# prototype1-with-charging-circut.net
KiCad netlist of a schematic drawn in EAGLE
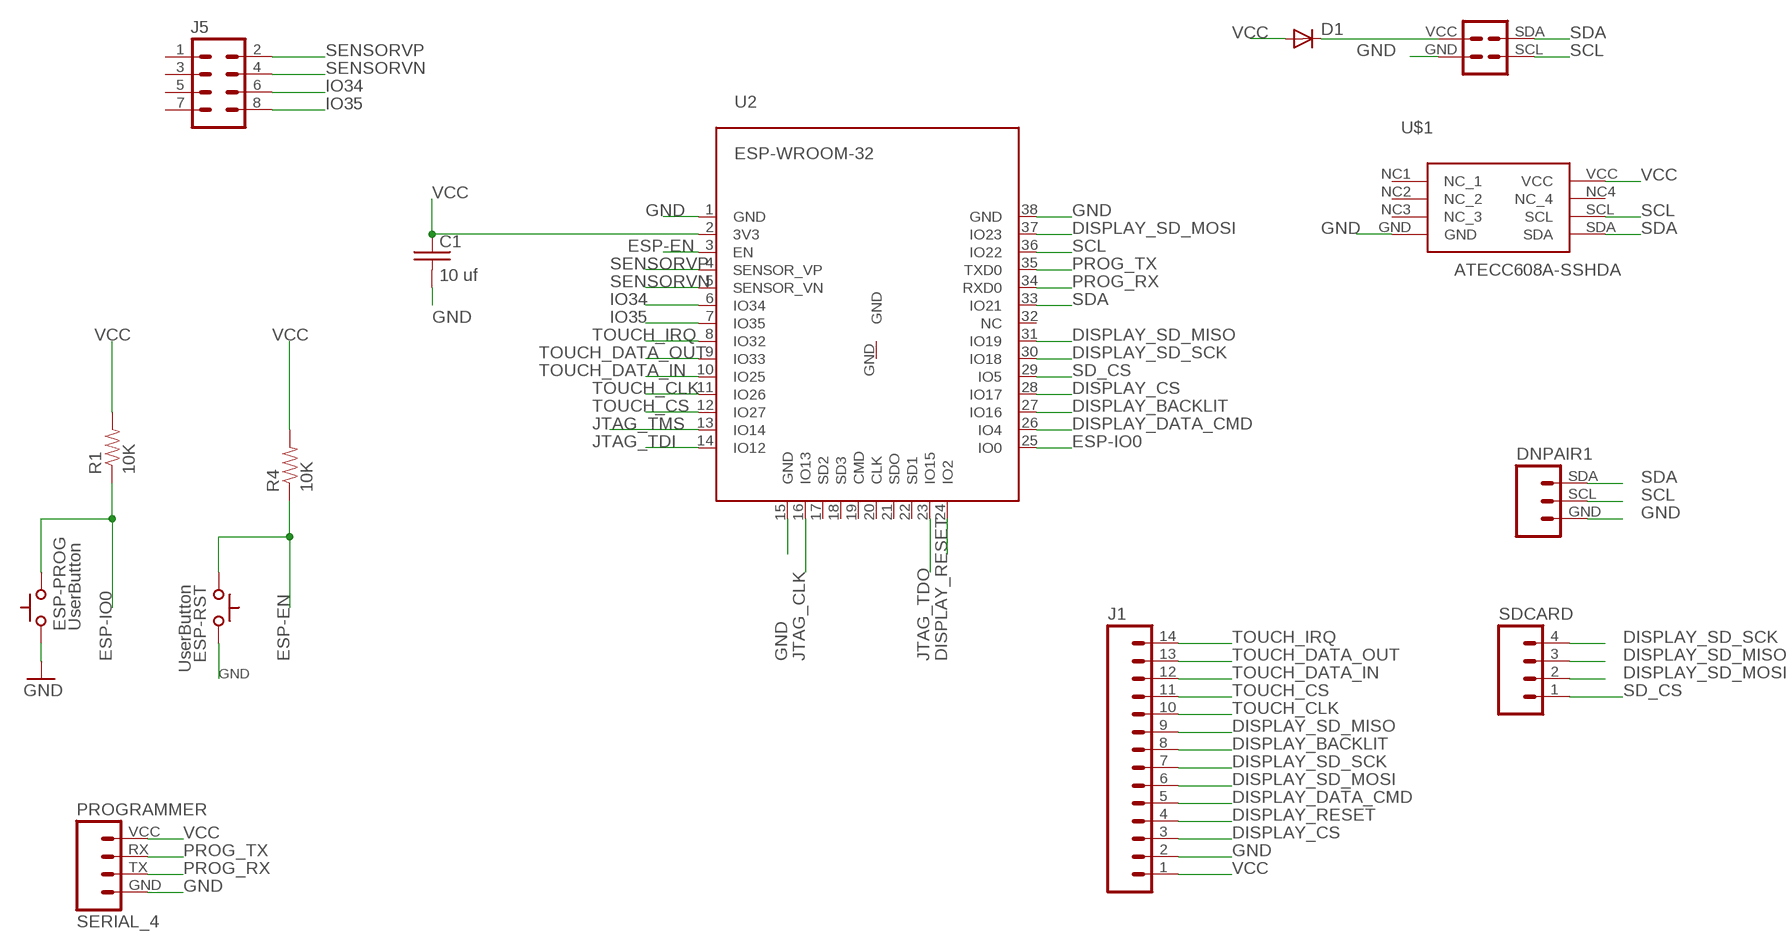
[diagram p0: schematic, sheet 1]
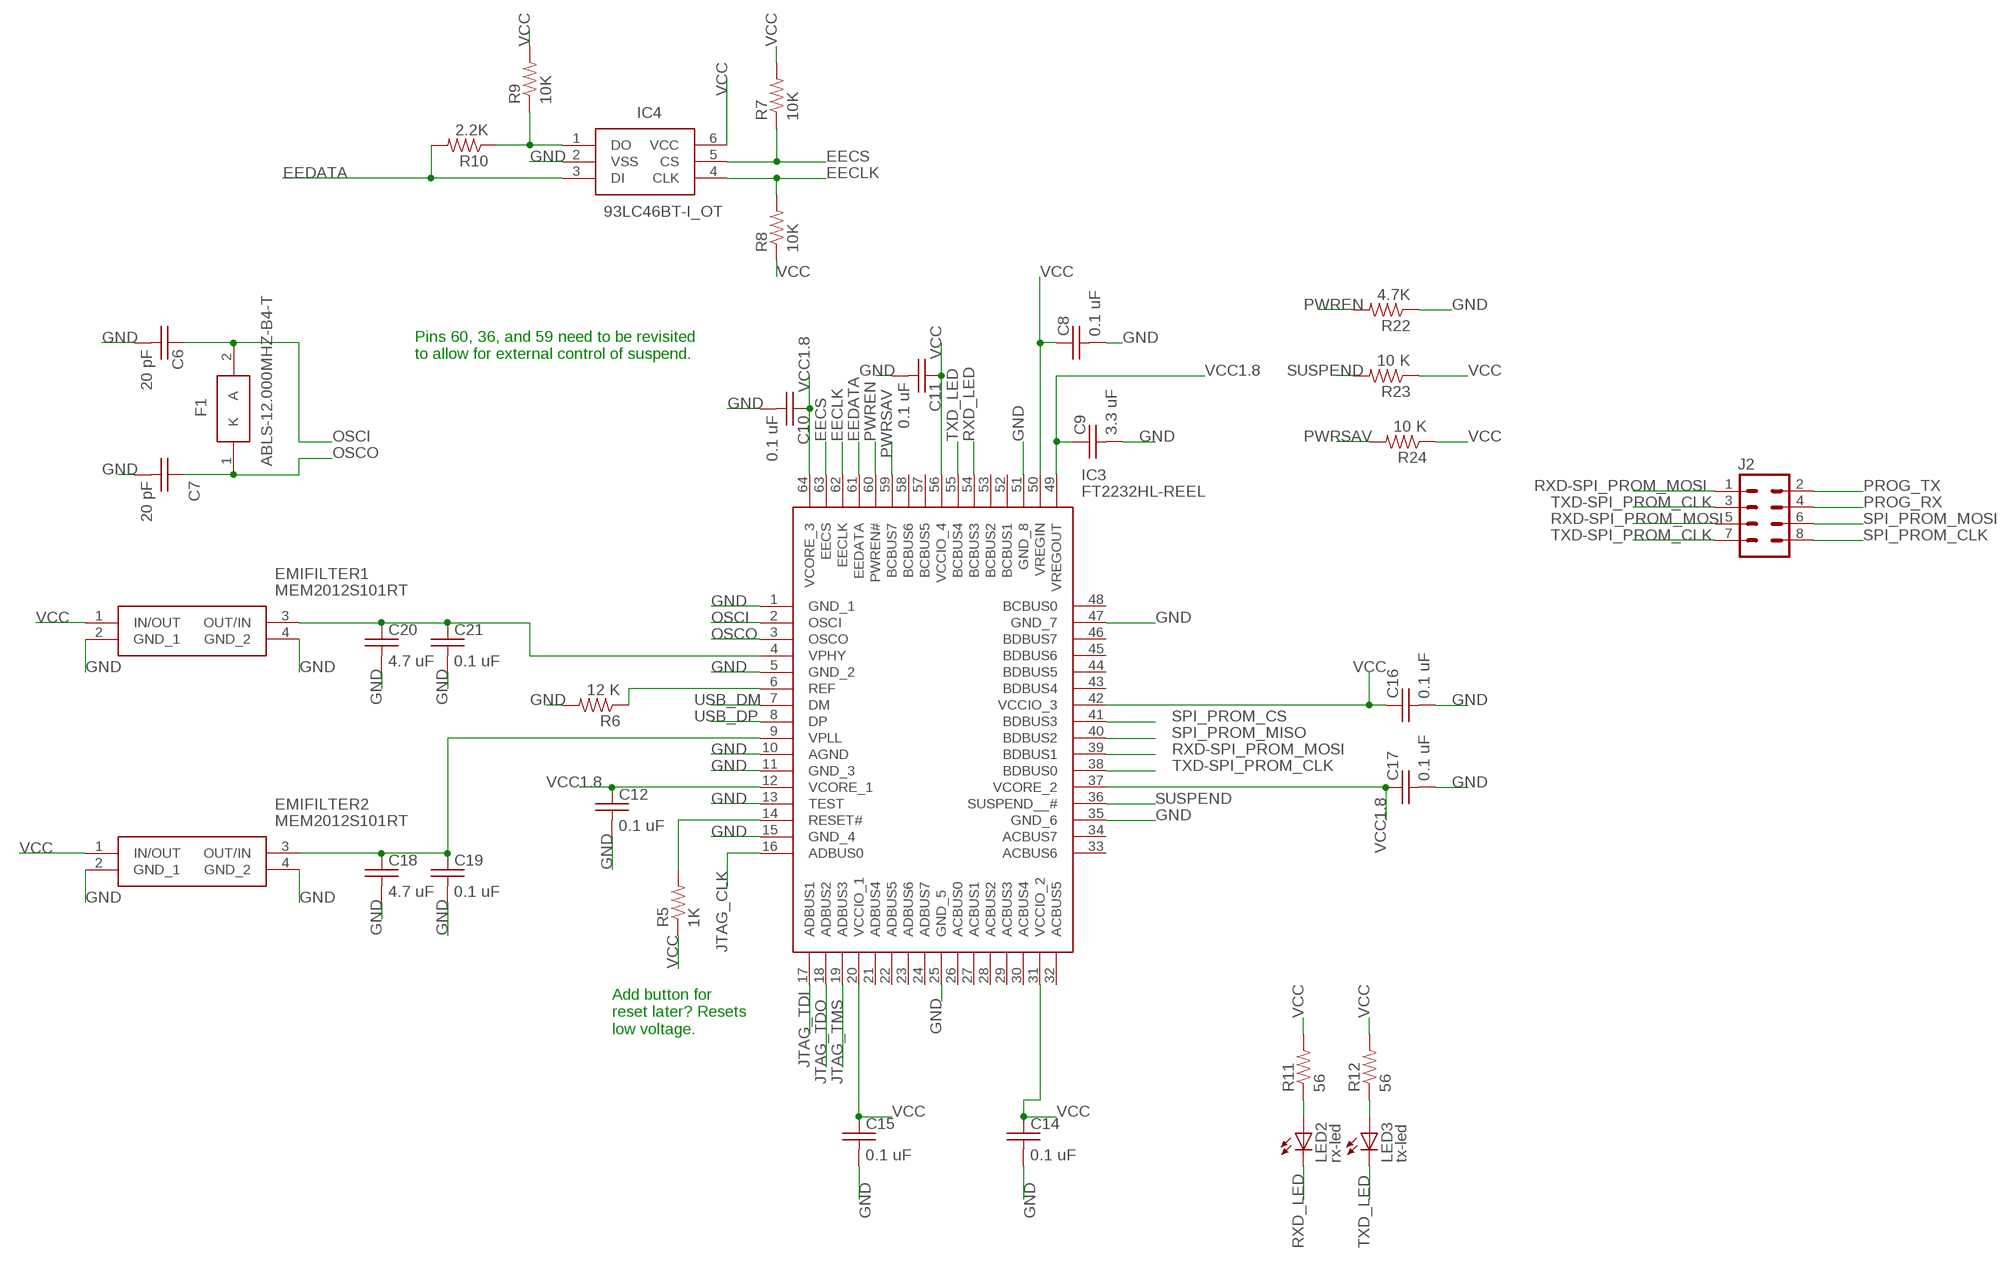
[diagram p1: schematic, sheet 2]
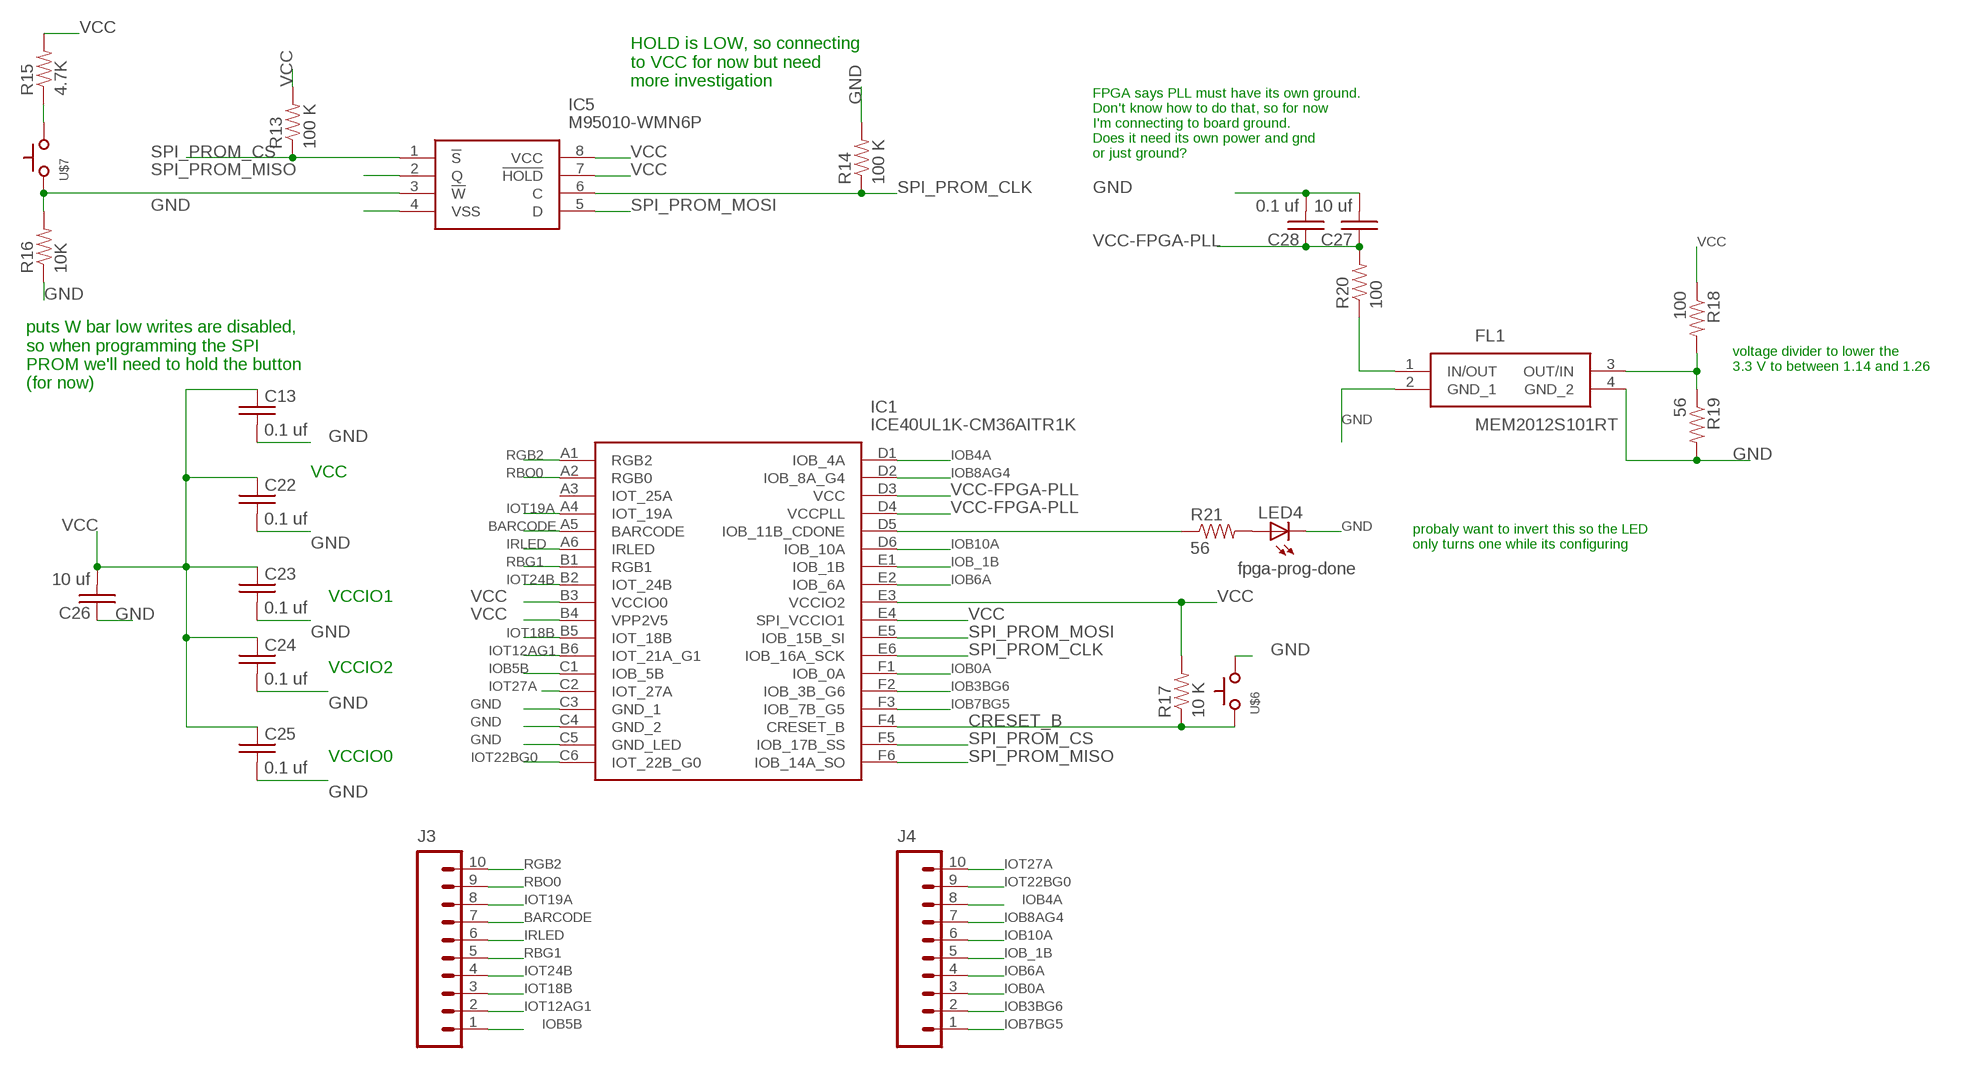
[diagram p2: schematic, sheet 3]
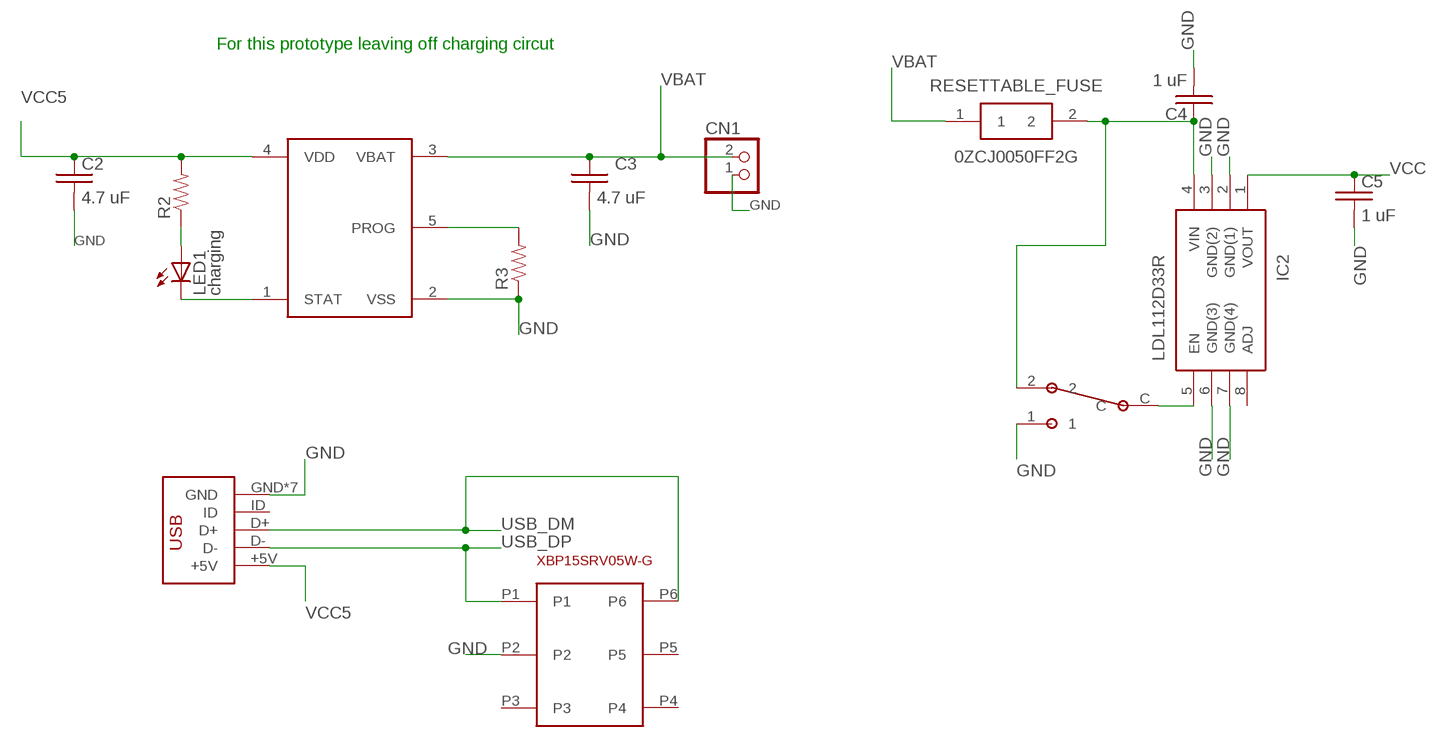
[diagram p3: schematic, sheet 4]

(export (version "E")
  (design (tool "Eeschema 10.0.6"))
  (components
    (comp (ref "C6")
      (value "20 pF")
      (footprint "eagle-import:C0805")
      (libsource (lib "eagle-import") (part "C-USC0805"))
    )
    (comp (ref "C7")
      (value "20 pF")
      (footprint "eagle-import:C0805")
      (libsource (lib "eagle-import") (part "C-USC0805"))
    )
    (comp (ref "C8")
      (value "0.1 uF")
      (footprint "eagle-import:C0805")
      (libsource (lib "eagle-import") (part "C-USC0805"))
    )
    (comp (ref "C9")
      (value "3.3 uF")
      (footprint "eagle-import:C0805")
      (libsource (lib "eagle-import") (part "C-USC0805"))
    )
    (comp (ref "C10")
      (value "0.1 uF")
      (footprint "eagle-import:C0805")
      (libsource (lib "eagle-import") (part "C-USC0805"))
    )
    (comp (ref "C11")
      (value "0.1 uF")
      (footprint "eagle-import:C0805")
      (libsource (lib "eagle-import") (part "C-USC0805"))
    )
    (comp (ref "C12")
      (value "0.1 uF")
      (footprint "eagle-import:C0805")
      (libsource (lib "eagle-import") (part "C-USC0805"))
    )
    (comp (ref "C14")
      (value "0.1 uF")
      (footprint "eagle-import:C0805")
      (libsource (lib "eagle-import") (part "C-USC0805"))
    )
    (comp (ref "C15")
      (value "0.1 uF")
      (footprint "eagle-import:C0805")
      (libsource (lib "eagle-import") (part "C-USC0805"))
    )
    (comp (ref "C16")
      (value "0.1 uF")
      (footprint "eagle-import:C0805")
      (libsource (lib "eagle-import") (part "C-USC0805"))
    )
    (comp (ref "C17")
      (value "0.1 uF")
      (footprint "eagle-import:C0805")
      (libsource (lib "eagle-import") (part "C-USC0805"))
    )
    (comp (ref "C18")
      (value "4.7 uF")
      (footprint "eagle-import:C0805")
      (libsource (lib "eagle-import") (part "C-USC0805"))
    )
    (comp (ref "C19")
      (value "0.1 uF")
      (footprint "eagle-import:C0805")
      (libsource (lib "eagle-import") (part "C-USC0805"))
    )
    (comp (ref "C20")
      (value "4.7 uF")
      (footprint "eagle-import:C0805")
      (libsource (lib "eagle-import") (part "C-USC0805"))
    )
    (comp (ref "C21")
      (value "0.1 uF")
      (footprint "eagle-import:C0805")
      (libsource (lib "eagle-import") (part "C-USC0805"))
    )
    (comp (ref "EMIFILTER1")
      (value "MEM2012S101RT")
      (footprint "eagle-import:MEM2012S101RT")
      (libsource (lib "eagle-import") (part "MEM2012S101RT"))
    )
    (comp (ref "EMIFILTER2")
      (value "MEM2012S101RT")
      (footprint "eagle-import:MEM2012S101RT")
      (libsource (lib "eagle-import") (part "MEM2012S101RT"))
    )
    (comp (ref "F1")
      (value "ABLS-12.000MHZ-B4-T")
      (footprint "eagle-import:HC_49US-(AT49)_1")
      (fields
        (field (name "MOUSER_PART_NUMBER") "815-ABLS-12.0M-T")
        (field (name "RS_PART_NUMBER") "1710207")
      )
      (libsource (lib "eagle-import") (part "ABLS-12.000MHZ-B4-T"))
    )
    (comp (ref "IC3")
      (value "FT2232HL-REEL")
      (footprint "eagle-import:QFP50P1200X1200X160-64N")
      (fields (field (name "MOUSER_PART_NUMBER") "895-FT2232HL"))
      (libsource (lib "eagle-import") (part "FT2232HL-REEL"))
    )
    (comp (ref "IC4")
      (value "93LC46BT-I_OT")
      (footprint "eagle-import:SOT95P270X145-6N")
      (fields
        (field (name "MANUFACTURER_PART_NUMBER") "93LC46BT-I/OT")
        (field (name "MOUSER_PART_NUMBER") "579-93LC46BT-I/OT")
      )
      (libsource (lib "eagle-import") (part "93LC46BT-I_OT"))
    )
    (comp (ref "J2")
      (value "M04X2")
      (footprint "eagle-import:2X4")
      (libsource (lib "eagle-import") (part "M04X2"))
    )
    (comp (ref "LED2")
      (value "rx-led")
      (footprint "eagle-import:LED3MM")
      (libsource (lib "eagle-import") (part "LED3MM"))
    )
    (comp (ref "LED3")
      (value "tx-led")
      (footprint "eagle-import:LED3MM")
      (libsource (lib "eagle-import") (part "LED3MM"))
    )
    (comp (ref "R5")
      (value "1K")
      (footprint "eagle-import:0805")
      (libsource (lib "eagle-import") (part "passives_RESISTOR0805-RES"))
    )
    (comp (ref "R6")
      (value "12 K")
      (footprint "eagle-import:0805")
      (libsource (lib "eagle-import") (part "passives_RESISTOR0805-RES"))
    )
    (comp (ref "R7")
      (value "10K")
      (footprint "eagle-import:0805")
      (libsource (lib "eagle-import") (part "passives_RESISTOR0805-RES"))
    )
    (comp (ref "R8")
      (value "10K")
      (footprint "eagle-import:0805")
      (libsource (lib "eagle-import") (part "passives_RESISTOR0805-RES"))
    )
    (comp (ref "R9")
      (value "10K")
      (footprint "eagle-import:0805")
      (libsource (lib "eagle-import") (part "passives_RESISTOR0805-RES"))
    )
    (comp (ref "R10")
      (value "2.2K")
      (footprint "eagle-import:0805")
      (libsource (lib "eagle-import") (part "passives_RESISTOR0805-RES"))
    )
    (comp (ref "R11")
      (value "56")
      (footprint "eagle-import:0805")
      (libsource (lib "eagle-import") (part "passives_RESISTOR0805-RES"))
    )
    (comp (ref "R12")
      (value "56")
      (footprint "eagle-import:0805")
      (libsource (lib "eagle-import") (part "passives_RESISTOR0805-RES"))
    )
    (comp (ref "R22")
      (value "4.7K")
      (footprint "eagle-import:0805")
      (libsource (lib "eagle-import") (part "passives_RESISTOR0805-RES"))
    )
    (comp (ref "R23")
      (value "10 K")
      (footprint "eagle-import:0805")
      (libsource (lib "eagle-import") (part "passives_RESISTOR0805-RES"))
    )
    (comp (ref "R24")
      (value "10 K")
      (footprint "eagle-import:0805")
      (libsource (lib "eagle-import") (part "passives_RESISTOR0805-RES"))
    )
    (comp (ref "C13")
      (value "0.1 uf")
      (footprint "eagle-import:C0805")
      (libsource (lib "eagle-import") (part "C-USC0805"))
    )
    (comp (ref "C22")
      (value "0.1 uf")
      (footprint "eagle-import:C0805")
      (libsource (lib "eagle-import") (part "C-USC0805"))
    )
    (comp (ref "C23")
      (value "0.1 uf")
      (footprint "eagle-import:C0805")
      (libsource (lib "eagle-import") (part "C-USC0805"))
    )
    (comp (ref "C24")
      (value "0.1 uf")
      (footprint "eagle-import:C0805")
      (libsource (lib "eagle-import") (part "C-USC0805"))
    )
    (comp (ref "C25")
      (value "0.1 uf")
      (footprint "eagle-import:C0805")
      (libsource (lib "eagle-import") (part "C-USC0805"))
    )
    (comp (ref "C26")
      (value "10 uf")
      (footprint "eagle-import:C0805")
      (libsource (lib "eagle-import") (part "C-USC0805"))
    )
    (comp (ref "C27")
      (value "10 uf")
      (footprint "eagle-import:C0805")
      (libsource (lib "eagle-import") (part "C-USC0805"))
    )
    (comp (ref "C28")
      (value "0.1 uf")
      (footprint "eagle-import:C0805")
      (libsource (lib "eagle-import") (part "C-USC0805"))
    )
    (comp (ref "FL1")
      (value "MEM2012S101RT")
      (footprint "eagle-import:MEM2012S101RT")
      (libsource (lib "eagle-import") (part "MEM2012S101RT"))
    )
    (comp (ref "IC1")
      (value "ICE40UL1K-CM36AITR1K")
      (footprint "eagle-import:BGA36C40P6X6_250X250X91")
      (fields (field (name "MOUSER_PART_NUMBER") "842-40UL1KCM36AITR1K"))
      (libsource (lib "eagle-import") (part "ICE40UL1K-CM36AITR1K"))
    )
    (comp (ref "IC5")
      (value "M95010-WMN6P")
      (footprint "eagle-import:SOIC127P600X175-8N")
      (fields
        (field (name "MOUSER_PART_NUMBER") "511-M95010-WMN6P")
        (field (name "RS_PART_NUMBER") "7147617")
      )
      (libsource (lib "eagle-import") (part "M95010-WMN6P"))
    )
    (comp (ref "J3")
      (value "M10SILK_FEMALE_PTH")
      (footprint "eagle-import:1X10")
      (libsource (lib "eagle-import") (part "M10SILK_FEMALE_PTH"))
    )
    (comp (ref "J4")
      (value "M10SILK_FEMALE_PTH")
      (footprint "eagle-import:1X10")
      (libsource (lib "eagle-import") (part "M10SILK_FEMALE_PTH"))
    )
    (comp (ref "LED4")
      (value "fpga-prog-done")
      (footprint "eagle-import:LED3MM")
      (libsource (lib "eagle-import") (part "LED3MM"))
    )
    (comp (ref "R13")
      (value "100 K")
      (footprint "eagle-import:0805")
      (libsource (lib "eagle-import") (part "passives_RESISTOR0805-RES"))
    )
    (comp (ref "R14")
      (value "100 K")
      (footprint "eagle-import:0805")
      (libsource (lib "eagle-import") (part "passives_RESISTOR0805-RES"))
    )
    (comp (ref "R15")
      (value "4.7K")
      (footprint "eagle-import:0805")
      (libsource (lib "eagle-import") (part "passives_RESISTOR0805-RES"))
    )
    (comp (ref "R16")
      (value "10K")
      (footprint "eagle-import:0805")
      (libsource (lib "eagle-import") (part "passives_RESISTOR0805-RES"))
    )
    (comp (ref "R17")
      (value "10 K")
      (footprint "eagle-import:0805")
      (libsource (lib "eagle-import") (part "passives_RESISTOR0805-RES"))
    )
    (comp (ref "R18")
      (value "100")
      (footprint "eagle-import:0805")
      (libsource (lib "eagle-import") (part "passives_RESISTOR0805-RES"))
    )
    (comp (ref "R19")
      (value "56")
      (footprint "eagle-import:0805")
      (libsource (lib "eagle-import") (part "passives_RESISTOR0805-RES"))
    )
    (comp (ref "R20")
      (value "100")
      (footprint "eagle-import:0805")
      (libsource (lib "eagle-import") (part "passives_RESISTOR0805-RES"))
    )
    (comp (ref "R21")
      (value "56")
      (footprint "eagle-import:0805")
      (libsource (lib "eagle-import") (part "passives_RESISTOR0805-RES"))
    )
    (comp (ref "U$6")
      (value "SWITCH_TACTILETACTILE-2PIN")
      (footprint "eagle-import:TACTILE-2PIN")
      (libsource (lib "eagle-import") (part "switches_SWITCH_TACTILETACTILE-2PIN"))
    )
    (comp (ref "U$7")
      (value "SWITCH_TACTILETACTILE-2PIN")
      (footprint "eagle-import:TACTILE-2PIN")
      (libsource (lib "eagle-import") (part "switches_SWITCH_TACTILETACTILE-2PIN"))
    )
    (comp (ref "C1")
      (value "10 uf")
      (footprint "eagle-import:C0805")
      (libsource (lib "eagle-import") (part "C-USC0805"))
    )
    (comp (ref "D1")
      (value "DIODESMA")
      (footprint "eagle-import:SMA-DIODE")
      (libsource (lib "eagle-import") (part "DIODESMA"))
    )
    (comp (ref "DNPAIR1")
      (value "DARKNET_8_PAIR_CONNECTORPTH")
      (footprint "eagle-import:1X03")
      (libsource (lib "eagle-import") (part "DARKNET_8_PAIR_CONNECTORPTH"))
    )
    (comp (ref "ESP-PROG")
      (value "UserButton")
      (footprint "eagle-import:TACTILE-2PIN-NARROW")
      (libsource (lib "eagle-import") (part "SWITCH_TACTILETACTILE-2PIN-NARROW"))
    )
    (comp (ref "ESP-RST")
      (value "UserButton")
      (footprint "eagle-import:TACTILE-2PIN-NARROW")
      (libsource (lib "eagle-import") (part "SWITCH_TACTILETACTILE-2PIN-NARROW"))
    )
    (comp (ref "J1")
      (value "M14")
      (footprint "eagle-import:1X14")
      (libsource (lib "eagle-import") (part "M14"))
    )
    (comp (ref "J5")
      (value "M04X2")
      (footprint "eagle-import:2X4")
      (libsource (lib "eagle-import") (part "M04X2"))
    )
    (comp (ref "PROGRAMMER")
      (value "SERIAL_4")
      (footprint "eagle-import:SERIAL_HEADER_4")
      (libsource (lib "eagle-import") (part "SERIAL_4"))
    )
    (comp (ref "R1")
      (value "10K")
      (footprint "eagle-import:0805")
      (libsource (lib "eagle-import") (part "RESISTOR0805-RES"))
    )
    (comp (ref "R4")
      (value "10K")
      (footprint "eagle-import:0805")
      (libsource (lib "eagle-import") (part "RESISTOR0805-RES"))
    )
    (comp (ref "SDCARD")
      (value "M04PTH")
      (footprint "eagle-import:1X04")
      (libsource (lib "eagle-import") (part "M04PTH"))
    )
    (comp (ref "SHITTY_ADDON")
      (value "SAO1")
      (footprint "eagle-import:DC26SHITTY_ADDON_CONNECTOR")
      (libsource (lib "eagle-import") (part "DC26_SHITTY_ADDON_CONNECTORPTH"))
    )
    (comp (ref "U$1")
      (value "ATECC608A-SSHDA")
      (footprint "eagle-import:8-SOIC")
      (libsource (lib "eagle-import") (part "ATECC608A-SSHDA"))
    )
    (comp (ref "U2")
      (value "ESP-WROOM-32")
      (footprint "eagle-import:ESP-WROOM-32")
      (libsource (lib "eagle-import") (part "ESP-WROOM-32"))
    )
    (comp (ref "C2")
      (value "4.7 uF")
      (footprint "eagle-import:C0805")
      (libsource (lib "eagle-import") (part "C-USC0805"))
    )
    (comp (ref "C3")
      (value "4.7 uF")
      (footprint "eagle-import:C0805")
      (libsource (lib "eagle-import") (part "C-USC0805"))
    )
    (comp (ref "C4")
      (value "1 uF")
      (footprint "eagle-import:C0805")
      (libsource (lib "eagle-import") (part "C-USC0805"))
    )
    (comp (ref "C5")
      (value "1 uF")
      (footprint "eagle-import:C0805")
      (libsource (lib "eagle-import") (part "C-USC0805"))
    )
    (comp (ref "CN1")
      (value "JST_2PIN-THM-RA")
      (footprint "eagle-import:JST-PH-2-THM-RA")
      (libsource (lib "eagle-import") (part "JST_2PIN-THM-RA"))
    )
    (comp (ref "IC2")
      (value "LDL112D33R")
      (footprint "eagle-import:SOIC127P600X175-8N")
      (libsource (lib "eagle-import") (part "LDL112D33R"))
    )
    (comp (ref "LED1")
      (value "charging")
      (footprint "eagle-import:LED-0603")
      (libsource (lib "eagle-import") (part "LED0603"))
    )
    (comp (ref "R2")
      (value "RESISTOR0805-RES")
      (footprint "eagle-import:0805")
      (libsource (lib "eagle-import") (part "passives_RESISTOR0805-RES"))
    )
    (comp (ref "R3")
      (value "RESISTOR0805-RES")
      (footprint "eagle-import:0805")
      (libsource (lib "eagle-import") (part "passives_RESISTOR0805-RES"))
    )
    (comp (ref "RESETTABLE_FUSE")
      (value "0ZCJ0050FF2G")
      (footprint "eagle-import:FUSC3216X55N")
      (libsource (lib "eagle-import") (part "0ZCJ0050FF2G"))
    )
    (comp (ref "U$2")
      (value "DX4R005JJ2DX4R005JJ2")
      (footprint "eagle-import:DX4R005JJ2")
      (libsource (lib "eagle-import") (part "DX4R005JJ2DX4R005JJ2"))
    )
    (comp (ref "U$3")
      (value "XBP15SRV05W-G")
      (footprint "eagle-import:SOT-26P-XBP15SRV05W-G")
      (fields (field (name "DIGI_KEY_PART_NUMBER") "893-1422-1-ND"))
      (libsource (lib "eagle-import") (part "XBP15SRV05W-G"))
    )
    (comp (ref "U$4")
      (value "DS21984E")
      (footprint "eagle-import:SOT23-5")
      (libsource (lib "eagle-import") (part "DS21984E"))
    )
    (comp (ref "U$5")
      (value "SWITCH_SPDT")
      (footprint "eagle-import:SPDT_SSAJ120100")
      (libsource (lib "eagle-import") (part "SWITCH_SPDT"))
    )
  )
  (nets
    (net (code "1") (name "BARCODE") (class "Default")
      (node (ref "IC1") (pin "A5") (pinfunction "BARCODE_A5") (pintype "bidirectional"))
      (node (ref "J3") (pin "7") (pinfunction "7_7") (pintype "passive"))
    )
    (net (code "2") (name "CRESET_B") (class "Default")
      (node (ref "IC1") (pin "F4") (pinfunction "CRESET_B_F4") (pintype "bidirectional"))
      (node (ref "R17") (pin "1") (pinfunction "1_1") (pintype "passive"))
      (node (ref "U$6") (pin "P$2") (pinfunction "C_P$2") (pintype "passive"))
    )
    (net (code "3") (name "DISPLAY_BACKLIT") (class "Default")
      (node (ref "J1") (pin "8") (pinfunction "8_8") (pintype "passive"))
      (node (ref "U2") (pin "27") (pinfunction "IO16_27") (pintype "bidirectional"))
    )
    (net (code "4") (name "DISPLAY_CS") (class "Default")
      (node (ref "J1") (pin "3") (pinfunction "3_3") (pintype "passive"))
      (node (ref "U2") (pin "28") (pinfunction "IO17_28") (pintype "bidirectional"))
    )
    (net (code "5") (name "DISPLAY_DATA_CMD") (class "Default")
      (node (ref "J1") (pin "5") (pinfunction "5_5") (pintype "passive"))
      (node (ref "U2") (pin "26") (pinfunction "IO4_26") (pintype "bidirectional"))
    )
    (net (code "6") (name "DISPLAY_RESET") (class "Default")
      (node (ref "J1") (pin "4") (pinfunction "4_4") (pintype "passive"))
      (node (ref "U2") (pin "24") (pinfunction "IO2_24") (pintype "bidirectional"))
    )
    (net (code "7") (name "DISPLAY_SD_MISO") (class "Default")
      (node (ref "J1") (pin "9") (pinfunction "9_9") (pintype "passive"))
      (node (ref "SDCARD") (pin "3") (pinfunction "3_3") (pintype "passive"))
      (node (ref "U2") (pin "31") (pinfunction "IO19_31") (pintype "bidirectional"))
    )
    (net (code "8") (name "DISPLAY_SD_MOSI") (class "Default")
      (node (ref "J1") (pin "6") (pinfunction "6_6") (pintype "passive"))
      (node (ref "SDCARD") (pin "2") (pinfunction "2_2") (pintype "passive"))
      (node (ref "U2") (pin "37") (pinfunction "IO23_37") (pintype "bidirectional"))
    )
    (net (code "9") (name "DISPLAY_SD_SCK") (class "Default")
      (node (ref "J1") (pin "7") (pinfunction "7_7") (pintype "passive"))
      (node (ref "SDCARD") (pin "4") (pinfunction "4_4") (pintype "passive"))
      (node (ref "U2") (pin "30") (pinfunction "IO18_30") (pintype "bidirectional"))
    )
    (net (code "10") (name "EECLK") (class "Default")
      (node (ref "IC3") (pin "62") (pinfunction "EECLK_62") (pintype "bidirectional"))
      (node (ref "IC4") (pin "4") (pinfunction "CLK_4") (pintype "input"))
      (node (ref "R8") (pin "2") (pinfunction "2_2") (pintype "passive"))
    )
    (net (code "11") (name "EECS") (class "Default")
      (node (ref "IC3") (pin "63") (pinfunction "EECS_63") (pintype "bidirectional"))
      (node (ref "IC4") (pin "5") (pinfunction "CS_5") (pintype "input"))
      (node (ref "R7") (pin "1") (pinfunction "1_1") (pintype "passive"))
    )
    (net (code "12") (name "EEDATA") (class "Default")
      (node (ref "IC3") (pin "61") (pinfunction "EEDATA_61") (pintype "bidirectional"))
      (node (ref "IC4") (pin "3") (pinfunction "DI_3") (pintype "bidirectional"))
      (node (ref "R10") (pin "2") (pinfunction "2_2") (pintype "passive"))
    )
    (net (code "13") (name "ESP-EN") (class "Default")
      (node (ref "ESP-RST") (pin "P$2") (pinfunction "C_P$2") (pintype "passive"))
      (node (ref "R4") (pin "1") (pinfunction "1_1") (pintype "passive"))
      (node (ref "U2") (pin "3") (pinfunction "EN_3") (pintype "bidirectional"))
    )
    (net (code "14") (name "ESP-IO0") (class "Default")
      (node (ref "ESP-PROG") (pin "P$1") (pinfunction "A_P$1") (pintype "passive"))
      (node (ref "R1") (pin "1") (pinfunction "1_1") (pintype "passive"))
      (node (ref "U2") (pin "25") (pinfunction "IO0_25") (pintype "bidirectional"))
    )
    (net (code "15") (name "GND") (class "Default")
      (node (ref "C1") (pin "2") (pinfunction "2_2") (pintype "passive"))
      (node (ref "C10") (pin "2") (pinfunction "2_2") (pintype "passive"))
      (node (ref "C11") (pin "2") (pinfunction "2_2") (pintype "passive"))
      (node (ref "C12") (pin "2") (pinfunction "2_2") (pintype "passive"))
      (node (ref "C13") (pin "2") (pinfunction "2_2") (pintype "passive"))
      (node (ref "C14") (pin "2") (pinfunction "2_2") (pintype "passive"))
      (node (ref "C15") (pin "2") (pinfunction "2_2") (pintype "passive"))
      (node (ref "C16") (pin "2") (pinfunction "2_2") (pintype "passive"))
      (node (ref "C17") (pin "2") (pinfunction "2_2") (pintype "passive"))
      (node (ref "C18") (pin "2") (pinfunction "2_2") (pintype "passive"))
      (node (ref "C19") (pin "2") (pinfunction "2_2") (pintype "passive"))
      (node (ref "C2") (pin "2") (pinfunction "2_2") (pintype "passive"))
      (node (ref "C20") (pin "2") (pinfunction "2_2") (pintype "passive"))
      (node (ref "C21") (pin "2") (pinfunction "2_2") (pintype "passive"))
      (node (ref "C22") (pin "2") (pinfunction "2_2") (pintype "passive"))
      (node (ref "C23") (pin "2") (pinfunction "2_2") (pintype "passive"))
      (node (ref "C24") (pin "2") (pinfunction "2_2") (pintype "passive"))
      (node (ref "C25") (pin "2") (pinfunction "2_2") (pintype "passive"))
      (node (ref "C26") (pin "1") (pinfunction "1_1") (pintype "passive"))
      (node (ref "C27") (pin "2") (pinfunction "2_2") (pintype "passive"))
      (node (ref "C28") (pin "2") (pinfunction "2_2") (pintype "passive"))
      (node (ref "C3") (pin "2") (pinfunction "2_2") (pintype "passive"))
      (node (ref "C4") (pin "2") (pinfunction "2_2") (pintype "passive"))
      (node (ref "C5") (pin "2") (pinfunction "2_2") (pintype "passive"))
      (node (ref "C6") (pin "2") (pinfunction "2_2") (pintype "passive"))
      (node (ref "C7") (pin "2") (pinfunction "2_2") (pintype "passive"))
      (node (ref "C8") (pin "2") (pinfunction "2_2") (pintype "passive"))
      (node (ref "C9") (pin "2") (pinfunction "2_2") (pintype "passive"))
      (node (ref "CN1") (pin "1") (pinfunction "2_1") (pintype "passive"))
      (node (ref "DNPAIR1") (pin "GND") (pinfunction "GND_GND") (pintype "power_in"))
      (node (ref "EMIFILTER1") (pin "2") (pinfunction "GND_1_2") (pintype "bidirectional"))
      (node (ref "EMIFILTER1") (pin "4") (pinfunction "GND_2_4") (pintype "bidirectional"))
      (node (ref "EMIFILTER2") (pin "2") (pinfunction "GND_1_2") (pintype "bidirectional"))
      (node (ref "EMIFILTER2") (pin "4") (pinfunction "GND_2_4") (pintype "bidirectional"))
      (node (ref "ESP-PROG") (pin "P$2") (pinfunction "C_P$2") (pintype "passive"))
      (node (ref "ESP-RST") (pin "P$1") (pinfunction "A_P$1") (pintype "passive"))
      (node (ref "FL1") (pin "2") (pinfunction "GND_1_2") (pintype "bidirectional"))
      (node (ref "FL1") (pin "4") (pinfunction "GND_2_4") (pintype "bidirectional"))
      (node (ref "IC1") (pin "C3") (pinfunction "GND_1_C3") (pintype "bidirectional"))
      (node (ref "IC1") (pin "C4") (pinfunction "GND_2_C4") (pintype "bidirectional"))
      (node (ref "IC1") (pin "C5") (pinfunction "GND_LED_C5") (pintype "bidirectional"))
      (node (ref "IC2") (pin "2") (pinfunction "GND(1)_2") (pintype "bidirectional"))
      (node (ref "IC2") (pin "3") (pinfunction "GND(2)_3") (pintype "bidirectional"))
      (node (ref "IC2") (pin "6") (pinfunction "GND(3)_6") (pintype "bidirectional"))
      (node (ref "IC2") (pin "7") (pinfunction "GND(4)_7") (pintype "bidirectional"))
      (node (ref "IC3") (pin "1") (pinfunction "GND_1_1") (pintype "bidirectional"))
      (node (ref "IC3") (pin "10") (pinfunction "AGND_10") (pintype "bidirectional"))
      (node (ref "IC3") (pin "11") (pinfunction "GND_3_11") (pintype "bidirectional"))
      (node (ref "IC3") (pin "13") (pinfunction "TEST_13") (pintype "bidirectional"))
      (node (ref "IC3") (pin "15") (pinfunction "GND_4_15") (pintype "bidirectional"))
      (node (ref "IC3") (pin "25") (pinfunction "GND_5_25") (pintype "bidirectional"))
      (node (ref "IC3") (pin "35") (pinfunction "GND_6_35") (pintype "bidirectional"))
      (node (ref "IC3") (pin "47") (pinfunction "GND_7_47") (pintype "bidirectional"))
      (node (ref "IC3") (pin "5") (pinfunction "GND_2_5") (pintype "bidirectional"))
      (node (ref "IC3") (pin "51") (pinfunction "GND_8_51") (pintype "bidirectional"))
      (node (ref "IC4") (pin "2") (pinfunction "VSS_2") (pintype "power_in"))
      (node (ref "IC5") (pin "4") (pinfunction "VSS_4") (pintype "power_in"))
      (node (ref "J1") (pin "2") (pinfunction "2_2") (pintype "passive"))
      (node (ref "LED4") (pin "K") (pinfunction "C_K") (pintype "output"))
      (node (ref "PROGRAMMER") (pin "GND") (pinfunction "GND_GND") (pintype "power_in"))
      (node (ref "R14") (pin "2") (pinfunction "2_2") (pintype "passive"))
      (node (ref "R16") (pin "1") (pinfunction "1_1") (pintype "passive"))
      (node (ref "R19") (pin "2") (pinfunction "2_2") (pintype "passive"))
      (node (ref "R22") (pin "1") (pinfunction "1_1") (pintype "passive"))
      (node (ref "R3") (pin "1") (pinfunction "1_1") (pintype "passive"))
      (node (ref "R6") (pin "2") (pinfunction "2_2") (pintype "passive"))
      (node (ref "SHITTY_ADDON") (pin "GND") (pinfunction "GND_GND") (pintype "power_in"))
      (node (ref "U$1") (pin "GND") (pinfunction "GND_GND") (pintype "power_in"))
      (node (ref "U$2") (pin "GND") (pinfunction "GND_GND") (pintype "bidirectional"))
      (node (ref "U$2") (pin "P$10") (pinfunction "GND_P$10") (pintype "bidirectional"))
      (node (ref "U$2") (pin "P$11") (pinfunction "GND_P$11") (pintype "bidirectional"))
      (node (ref "U$2") (pin "P$6") (pinfunction "GND_P$6") (pintype "bidirectional"))
      (node (ref "U$2") (pin "P$7") (pinfunction "GND_P$7") (pintype "bidirectional"))
      (node (ref "U$2") (pin "P$8") (pinfunction "GND_P$8") (pintype "bidirectional"))
      (node (ref "U$2") (pin "P$9") (pinfunction "GND_P$9") (pintype "bidirectional"))
      (node (ref "U$3") (pin "P2") (pinfunction "P2_P2") (pintype "bidirectional"))
      (node (ref "U$4") (pin "2") (pinfunction "VSS_2") (pintype "bidirectional"))
      (node (ref "U$5") (pin "1") (pinfunction "1_1") (pintype "bidirectional"))
      (node (ref "U$6") (pin "P$1") (pinfunction "A_P$1") (pintype "passive"))
      (node (ref "U2") (pin "1") (pinfunction "GND_1") (pintype "bidirectional"))
      (node (ref "U2") (pin "15") (pinfunction "GND_15") (pintype "bidirectional"))
      (node (ref "U2") (pin "38") (pinfunction "GND_38") (pintype "bidirectional"))
    )
    (net (code "16") (name "IO34") (class "Default")
      (node (ref "J5") (pin "6") (pinfunction "6_6") (pintype "passive"))
      (node (ref "U2") (pin "6") (pinfunction "IO34_6") (pintype "bidirectional"))
    )
    (net (code "17") (name "IO35") (class "Default")
      (node (ref "J5") (pin "8") (pinfunction "8_8") (pintype "passive"))
      (node (ref "U2") (pin "7") (pinfunction "IO35_7") (pintype "bidirectional"))
    )
    (net (code "18") (name "IOB0A") (class "Default")
      (node (ref "IC1") (pin "F1") (pinfunction "IOB_0A_F1") (pintype "bidirectional"))
      (node (ref "J4") (pin "3") (pinfunction "3_3") (pintype "passive"))
    )
    (net (code "19") (name "IOB3BG6") (class "Default")
      (node (ref "IC1") (pin "F2") (pinfunction "IOB_3B_G6_F2") (pintype "bidirectional"))
      (node (ref "J4") (pin "2") (pinfunction "2_2") (pintype "passive"))
    )
    (net (code "20") (name "IOB4A") (class "Default")
      (node (ref "IC1") (pin "D1") (pinfunction "IOB_4A_D1") (pintype "bidirectional"))
      (node (ref "J4") (pin "8") (pinfunction "8_8") (pintype "passive"))
    )
    (net (code "21") (name "IOB5B") (class "Default")
      (node (ref "IC1") (pin "C1") (pinfunction "IOB_5B_C1") (pintype "bidirectional"))
      (node (ref "J3") (pin "1") (pinfunction "1_1") (pintype "passive"))
    )
    (net (code "22") (name "IOB6A") (class "Default")
      (node (ref "IC1") (pin "E2") (pinfunction "IOB_6A_E2") (pintype "bidirectional"))
      (node (ref "J4") (pin "4") (pinfunction "4_4") (pintype "passive"))
    )
    (net (code "23") (name "IOB7BG5") (class "Default")
      (node (ref "IC1") (pin "F3") (pinfunction "IOB_7B_G5_F3") (pintype "bidirectional"))
      (node (ref "J4") (pin "1") (pinfunction "1_1") (pintype "passive"))
    )
    (net (code "24") (name "IOB8AG4") (class "Default")
      (node (ref "IC1") (pin "D2") (pinfunction "IOB_8A_G4_D2") (pintype "bidirectional"))
      (node (ref "J4") (pin "7") (pinfunction "7_7") (pintype "passive"))
    )
    (net (code "25") (name "IOB10A") (class "Default")
      (node (ref "IC1") (pin "D6") (pinfunction "IOB_10A_D6") (pintype "bidirectional"))
      (node (ref "J4") (pin "6") (pinfunction "6_6") (pintype "passive"))
    )
    (net (code "26") (name "IOB_1B") (class "Default")
      (node (ref "IC1") (pin "E1") (pinfunction "IOB_1B_E1") (pintype "bidirectional"))
      (node (ref "J4") (pin "5") (pinfunction "5_5") (pintype "passive"))
    )
    (net (code "27") (name "IOT12AG1") (class "Default")
      (node (ref "IC1") (pin "B6") (pinfunction "IOT_21A_G1_B6") (pintype "bidirectional"))
      (node (ref "J3") (pin "2") (pinfunction "2_2") (pintype "passive"))
    )
    (net (code "28") (name "IOT18B") (class "Default")
      (node (ref "IC1") (pin "B5") (pinfunction "IOT_18B_B5") (pintype "bidirectional"))
      (node (ref "J3") (pin "3") (pinfunction "3_3") (pintype "passive"))
    )
    (net (code "29") (name "IOT19A") (class "Default")
      (node (ref "IC1") (pin "A4") (pinfunction "IOT_19A_A4") (pintype "bidirectional"))
      (node (ref "J3") (pin "8") (pinfunction "8_8") (pintype "passive"))
    )
    (net (code "30") (name "IOT22BG0") (class "Default")
      (node (ref "IC1") (pin "C6") (pinfunction "IOT_22B_G0_C6") (pintype "bidirectional"))
      (node (ref "J4") (pin "9") (pinfunction "9_9") (pintype "passive"))
    )
    (net (code "31") (name "IOT24B") (class "Default")
      (node (ref "IC1") (pin "B2") (pinfunction "IOT_24B_B2") (pintype "bidirectional"))
      (node (ref "J3") (pin "4") (pinfunction "4_4") (pintype "passive"))
    )
    (net (code "32") (name "IOT27A") (class "Default")
      (node (ref "IC1") (pin "C2") (pinfunction "IOT_27A_C2") (pintype "bidirectional"))
      (node (ref "J4") (pin "10") (pinfunction "10_10") (pintype "passive"))
    )
    (net (code "33") (name "IRLED") (class "Default")
      (node (ref "IC1") (pin "A6") (pinfunction "IRLED_A6") (pintype "bidirectional"))
      (node (ref "J3") (pin "6") (pinfunction "6_6") (pintype "passive"))
    )
    (net (code "34") (name "JTAG_CLK") (class "Default")
      (node (ref "IC3") (pin "16") (pinfunction "ADBUS0_16") (pintype "bidirectional"))
      (node (ref "U2") (pin "16") (pinfunction "IO13_16") (pintype "bidirectional"))
    )
    (net (code "35") (name "JTAG_TDI") (class "Default")
      (node (ref "IC3") (pin "17") (pinfunction "ADBUS1_17") (pintype "bidirectional"))
      (node (ref "U2") (pin "14") (pinfunction "IO12_14") (pintype "bidirectional"))
    )
    (net (code "36") (name "JTAG_TDO") (class "Default")
      (node (ref "IC3") (pin "18") (pinfunction "ADBUS2_18") (pintype "bidirectional"))
      (node (ref "U2") (pin "23") (pinfunction "IO15_23") (pintype "bidirectional"))
    )
    (net (code "37") (name "JTAG_TMS") (class "Default")
      (node (ref "IC3") (pin "19") (pinfunction "ADBUS3_19") (pintype "bidirectional"))
      (node (ref "U2") (pin "13") (pinfunction "IO14_13") (pintype "bidirectional"))
    )
    (net (code "38") (name "Net-(D1-PadC)") (class "Default")
      (node (ref "D1") (pin "C") (pinfunction "C_C") (pintype "passive"))
      (node (ref "SHITTY_ADDON") (pin "VCC") (pinfunction "VCC_VCC") (pintype "power_in"))
    )
    (net (code "39") (name "Net-(EMIFILTER1-OUT{slash}IN)") (class "Default")
      (node (ref "C20") (pin "1") (pinfunction "1_1") (pintype "passive"))
      (node (ref "C21") (pin "1") (pinfunction "1_1") (pintype "passive"))
      (node (ref "EMIFILTER1") (pin "3") (pinfunction "OUT/IN_3") (pintype "bidirectional"))
      (node (ref "IC3") (pin "4") (pinfunction "VPHY_4") (pintype "bidirectional"))
    )
    (net (code "40") (name "Net-(EMIFILTER2-OUT{slash}IN)") (class "Default")
      (node (ref "C18") (pin "1") (pinfunction "1_1") (pintype "passive"))
      (node (ref "C19") (pin "1") (pinfunction "1_1") (pintype "passive"))
      (node (ref "EMIFILTER2") (pin "3") (pinfunction "OUT/IN_3") (pintype "bidirectional"))
      (node (ref "IC3") (pin "9") (pinfunction "VPLL_9") (pintype "bidirectional"))
    )
    (net (code "41") (name "Net-(FL1-IN{slash}OUT)") (class "Default")
      (node (ref "FL1") (pin "1") (pinfunction "IN/OUT_1") (pintype "bidirectional"))
      (node (ref "R20") (pin "1") (pinfunction "1_1") (pintype "passive"))
    )
    (net (code "42") (name "Net-(FL1-OUT{slash}IN)") (class "Default")
      (node (ref "FL1") (pin "3") (pinfunction "OUT/IN_3") (pintype "bidirectional"))
      (node (ref "R18") (pin "2") (pinfunction "2_2") (pintype "passive"))
      (node (ref "R19") (pin "1") (pinfunction "1_1") (pintype "passive"))
    )
    (net (code "43") (name "Net-(IC1-IOB_11B_CDONE)") (class "Default")
      (node (ref "IC1") (pin "D5") (pinfunction "IOB_11B_CDONE_D5") (pintype "bidirectional"))
      (node (ref "R21") (pin "1") (pinfunction "1_1") (pintype "passive"))
    )
    (net (code "44") (name "Net-(IC2-EN)") (class "Default")
      (node (ref "IC2") (pin "5") (pinfunction "EN_5") (pintype "bidirectional"))
      (node (ref "U$5") (pin "C") (pinfunction "C_C") (pintype "bidirectional"))
    )
    (net (code "45") (name "Net-(IC2-VIN)") (class "Default")
      (node (ref "C4") (pin "1") (pinfunction "1_1") (pintype "passive"))
      (node (ref "IC2") (pin "4") (pinfunction "VIN_4") (pintype "bidirectional"))
      (node (ref "RESETTABLE_FUSE") (pin "2") (pinfunction "2_2") (pintype "passive"))
      (node (ref "U$5") (pin "2") (pinfunction "2_2") (pintype "bidirectional"))
    )
    (net (code "46") (name "Net-(IC3-REF)") (class "Default")
      (node (ref "IC3") (pin "6") (pinfunction "REF_6") (pintype "bidirectional"))
      (node (ref "R6") (pin "1") (pinfunction "1_1") (pintype "passive"))
    )
    (net (code "47") (name "Net-(IC3-RESET#)") (class "Default")
      (node (ref "IC3") (pin "14") (pinfunction "RESET#_14") (pintype "bidirectional"))
      (node (ref "R5") (pin "2") (pinfunction "2_2") (pintype "passive"))
    )
    (net (code "48") (name "Net-(IC4-DO)") (class "Default")
      (node (ref "IC4") (pin "1") (pinfunction "DO_1") (pintype "bidirectional"))
      (node (ref "R10") (pin "1") (pinfunction "1_1") (pintype "passive"))
      (node (ref "R9") (pin "1") (pinfunction "1_1") (pintype "passive"))
    )
    (net (code "49") (name "Net-(IC5-~{W})") (class "Default")
      (node (ref "IC5") (pin "3") (pinfunction "~{W}_3") (pintype "bidirectional"))
      (node (ref "R16") (pin "2") (pinfunction "2_2") (pintype "passive"))
      (node (ref "U$7") (pin "P$2") (pinfunction "C_P$2") (pintype "passive"))
    )
    (net (code "50") (name "Net-(LED1-PadA)") (class "Default")
      (node (ref "LED1") (pin "A") (pinfunction "A_A") (pintype "input"))
      (node (ref "R2") (pin "1") (pinfunction "1_1") (pintype "passive"))
    )
    (net (code "51") (name "Net-(LED2-PadA)") (class "Default")
      (node (ref "LED2") (pin "A") (pinfunction "A_A") (pintype "input"))
      (node (ref "R11") (pin "1") (pinfunction "1_1") (pintype "passive"))
    )
    (net (code "52") (name "Net-(LED3-PadA)") (class "Default")
      (node (ref "LED3") (pin "A") (pinfunction "A_A") (pintype "input"))
      (node (ref "R12") (pin "1") (pinfunction "1_1") (pintype "passive"))
    )
    (net (code "53") (name "Net-(LED4-PadA)") (class "Default")
      (node (ref "LED4") (pin "A") (pinfunction "A_A") (pintype "input"))
      (node (ref "R21") (pin "2") (pinfunction "2_2") (pintype "passive"))
    )
    (net (code "54") (name "Net-(U$4-PROG)") (class "Default")
      (node (ref "R3") (pin "2") (pinfunction "2_2") (pintype "passive"))
      (node (ref "U$4") (pin "5") (pinfunction "PROG_5") (pintype "bidirectional"))
    )
    (net (code "55") (name "Net-(U$4-STAT)") (class "Default")
      (node (ref "LED1") (pin "C") (pinfunction "C_C") (pintype "output"))
      (node (ref "U$4") (pin "1") (pinfunction "STAT_1") (pintype "bidirectional"))
    )
    (net (code "56") (name "Net-(U$7-A)") (class "Default")
      (node (ref "R15") (pin "1") (pinfunction "1_1") (pintype "passive"))
      (node (ref "U$7") (pin "P$1") (pinfunction "A_P$1") (pintype "passive"))
    )
    (net (code "57") (name "OSCI") (class "Default")
      (node (ref "C6") (pin "1") (pinfunction "1_1") (pintype "passive"))
      (node (ref "F1") (pin "2") (pinfunction "A_2") (pintype "bidirectional"))
      (node (ref "IC3") (pin "2") (pinfunction "OSCI_2") (pintype "bidirectional"))
    )
    (net (code "58") (name "OSCO") (class "Default")
      (node (ref "C7") (pin "1") (pinfunction "1_1") (pintype "passive"))
      (node (ref "F1") (pin "1") (pinfunction "K_1") (pintype "bidirectional"))
      (node (ref "IC3") (pin "3") (pinfunction "OSCO_3") (pintype "bidirectional"))
    )
    (net (code "59") (name "PROG_RX") (class "Default")
      (node (ref "J2") (pin "4") (pinfunction "4_4") (pintype "passive"))
      (node (ref "PROGRAMMER") (pin "TX") (pinfunction "TX_TX") (pintype "input"))
      (node (ref "U2") (pin "34") (pinfunction "RXD0_34") (pintype "bidirectional"))
    )
    (net (code "60") (name "PROG_TX") (class "Default")
      (node (ref "J2") (pin "2") (pinfunction "2_2") (pintype "passive"))
      (node (ref "PROGRAMMER") (pin "RX") (pinfunction "RX_RX") (pintype "bidirectional"))
      (node (ref "U2") (pin "35") (pinfunction "TXD0_35") (pintype "bidirectional"))
    )
    (net (code "61") (name "PWREN") (class "Default")
      (node (ref "IC3") (pin "60") (pinfunction "PWREN#_60") (pintype "bidirectional"))
      (node (ref "R22") (pin "2") (pinfunction "2_2") (pintype "passive"))
    )
    (net (code "62") (name "PWRSAV") (class "Default")
      (node (ref "IC3") (pin "59") (pinfunction "BCBUS7_59") (pintype "bidirectional"))
      (node (ref "R24") (pin "2") (pinfunction "2_2") (pintype "passive"))
    )
    (net (code "63") (name "RBG1") (class "Default")
      (node (ref "IC1") (pin "B1") (pinfunction "RGB1_B1") (pintype "bidirectional"))
      (node (ref "J3") (pin "5") (pinfunction "5_5") (pintype "passive"))
    )
    (net (code "64") (name "RBO0") (class "Default")
      (node (ref "IC1") (pin "A2") (pinfunction "RGB0_A2") (pintype "bidirectional"))
      (node (ref "J3") (pin "9") (pinfunction "9_9") (pintype "passive"))
    )
    (net (code "65") (name "RGB2") (class "Default")
      (node (ref "IC1") (pin "A1") (pinfunction "RGB2_A1") (pintype "bidirectional"))
      (node (ref "J3") (pin "10") (pinfunction "10_10") (pintype "passive"))
    )
    (net (code "66") (name "RXD-SPI_PROM_MOSI") (class "Default")
      (node (ref "IC3") (pin "39") (pinfunction "BDBUS1_39") (pintype "bidirectional"))
      (node (ref "J2") (pin "1") (pinfunction "1_1") (pintype "passive"))
      (node (ref "J2") (pin "5") (pinfunction "5_5") (pintype "passive"))
    )
    (net (code "67") (name "RXD_LED") (class "Default")
      (node (ref "IC3") (pin "54") (pinfunction "BCBUS3_54") (pintype "bidirectional"))
      (node (ref "LED2") (pin "K") (pinfunction "C_K") (pintype "output"))
    )
    (net (code "68") (name "SCL") (class "Default")
      (node (ref "DNPAIR1") (pin "SCL") (pinfunction "SCL_SCL") (pintype "bidirectional"))
      (node (ref "SHITTY_ADDON") (pin "SCL") (pinfunction "SCL_SCL") (pintype "bidirectional"))
      (node (ref "U$1") (pin "SCL") (pinfunction "SCL_SCL") (pintype "bidirectional"))
      (node (ref "U2") (pin "36") (pinfunction "IO22_36") (pintype "bidirectional"))
    )
    (net (code "69") (name "SDA") (class "Default")
      (node (ref "DNPAIR1") (pin "SDA") (pinfunction "SDA_SDA") (pintype "bidirectional"))
      (node (ref "SHITTY_ADDON") (pin "SDA") (pinfunction "SDA_SDA") (pintype "bidirectional"))
      (node (ref "U$1") (pin "SDA") (pinfunction "SDA_SDA") (pintype "bidirectional"))
      (node (ref "U2") (pin "33") (pinfunction "IO21_33") (pintype "bidirectional"))
    )
    (net (code "70") (name "SD_CS") (class "Default")
      (node (ref "SDCARD") (pin "1") (pinfunction "1_1") (pintype "passive"))
      (node (ref "U2") (pin "29") (pinfunction "IO5_29") (pintype "bidirectional"))
    )
    (net (code "71") (name "SENSORVN") (class "Default")
      (node (ref "J5") (pin "4") (pinfunction "4_4") (pintype "passive"))
      (node (ref "U2") (pin "5") (pinfunction "SENSOR_VN_5") (pintype "bidirectional"))
    )
    (net (code "72") (name "SENSORVP") (class "Default")
      (node (ref "J5") (pin "2") (pinfunction "2_2") (pintype "passive"))
      (node (ref "U2") (pin "4") (pinfunction "SENSOR_VP_4") (pintype "bidirectional"))
    )
    (net (code "73") (name "SPI_PROM_CLK") (class "Default")
      (node (ref "IC1") (pin "E6") (pinfunction "IOB_16A_SCK_E6") (pintype "bidirectional"))
      (node (ref "IC5") (pin "6") (pinfunction "C_6") (pintype "bidirectional"))
      (node (ref "J2") (pin "8") (pinfunction "8_8") (pintype "passive"))
      (node (ref "R14") (pin "1") (pinfunction "1_1") (pintype "passive"))
    )
    (net (code "74") (name "SPI_PROM_CS") (class "Default")
      (node (ref "IC1") (pin "F5") (pinfunction "IOB_17B_SS_F5") (pintype "bidirectional"))
      (node (ref "IC3") (pin "41") (pinfunction "BDBUS3_41") (pintype "bidirectional"))
      (node (ref "IC5") (pin "1") (pinfunction "~{S}_1") (pintype "bidirectional"))
      (node (ref "R13") (pin "1") (pinfunction "1_1") (pintype "passive"))
    )
    (net (code "75") (name "SPI_PROM_MISO") (class "Default")
      (node (ref "IC1") (pin "F6") (pinfunction "IOB_14A_SO_F6") (pintype "bidirectional"))
      (node (ref "IC3") (pin "40") (pinfunction "BDBUS2_40") (pintype "bidirectional"))
      (node (ref "IC5") (pin "2") (pinfunction "Q_2") (pintype "output"))
    )
    (net (code "76") (name "SPI_PROM_MOSI") (class "Default")
      (node (ref "IC1") (pin "E5") (pinfunction "IOB_15B_SI_E5") (pintype "bidirectional"))
      (node (ref "IC5") (pin "5") (pinfunction "D_5") (pintype "input"))
      (node (ref "J2") (pin "6") (pinfunction "6_6") (pintype "passive"))
    )
    (net (code "77") (name "SUSPEND") (class "Default")
      (node (ref "IC3") (pin "36") (pinfunction "SUSPEND__#_36") (pintype "bidirectional"))
      (node (ref "R23") (pin "2") (pinfunction "2_2") (pintype "passive"))
    )
    (net (code "78") (name "TOUCH_CLK") (class "Default")
      (node (ref "J1") (pin "10") (pinfunction "10_10") (pintype "passive"))
      (node (ref "U2") (pin "11") (pinfunction "IO26_11") (pintype "bidirectional"))
    )
    (net (code "79") (name "TOUCH_CS") (class "Default")
      (node (ref "J1") (pin "11") (pinfunction "11_11") (pintype "passive"))
      (node (ref "U2") (pin "12") (pinfunction "IO27_12") (pintype "bidirectional"))
    )
    (net (code "80") (name "TOUCH_DATA_IN") (class "Default")
      (node (ref "J1") (pin "12") (pinfunction "12_12") (pintype "passive"))
      (node (ref "U2") (pin "10") (pinfunction "IO25_10") (pintype "bidirectional"))
    )
    (net (code "81") (name "TOUCH_DATA_OUT") (class "Default")
      (node (ref "J1") (pin "13") (pinfunction "13_13") (pintype "passive"))
      (node (ref "U2") (pin "9") (pinfunction "IO33_9") (pintype "bidirectional"))
    )
    (net (code "82") (name "TOUCH_IRQ") (class "Default")
      (node (ref "J1") (pin "14") (pinfunction "14_14") (pintype "passive"))
      (node (ref "U2") (pin "8") (pinfunction "IO32_8") (pintype "bidirectional"))
    )
    (net (code "83") (name "TXD-SPI_PROM_CLK") (class "Default")
      (node (ref "IC3") (pin "38") (pinfunction "BDBUS0_38") (pintype "bidirectional"))
      (node (ref "J2") (pin "3") (pinfunction "3_3") (pintype "passive"))
      (node (ref "J2") (pin "7") (pinfunction "7_7") (pintype "passive"))
    )
    (net (code "84") (name "TXD_LED") (class "Default")
      (node (ref "IC3") (pin "55") (pinfunction "BCBUS4_55") (pintype "bidirectional"))
      (node (ref "LED3") (pin "K") (pinfunction "C_K") (pintype "output"))
    )
    (net (code "85") (name "USB_DM") (class "Default")
      (node (ref "IC3") (pin "7") (pinfunction "DM_7") (pintype "bidirectional"))
      (node (ref "U$2") (pin "D+") (pinfunction "D+_D+") (pintype "bidirectional"))
      (node (ref "U$3") (pin "P6") (pinfunction "P6_P6") (pintype "bidirectional"))
    )
    (net (code "86") (name "USB_DP") (class "Default")
      (node (ref "IC3") (pin "8") (pinfunction "DP_8") (pintype "bidirectional"))
      (node (ref "U$2") (pin "D-") (pinfunction "D-_D-") (pintype "bidirectional"))
      (node (ref "U$3") (pin "P1") (pinfunction "P1_P1") (pintype "bidirectional"))
    )
    (net (code "87") (name "VBAT") (class "Default")
      (node (ref "C3") (pin "1") (pinfunction "1_1") (pintype "passive"))
      (node (ref "CN1") (pin "2") (pinfunction "1_2") (pintype "passive"))
      (node (ref "RESETTABLE_FUSE") (pin "1") (pinfunction "1_1") (pintype "passive"))
      (node (ref "U$4") (pin "3") (pinfunction "VBAT_3") (pintype "bidirectional"))
    )
    (net (code "88") (name "VCC") (class "Default")
      (node (ref "C1") (pin "1") (pinfunction "1_1") (pintype "passive"))
      (node (ref "C11") (pin "1") (pinfunction "1_1") (pintype "passive"))
      (node (ref "C13") (pin "1") (pinfunction "1_1") (pintype "passive"))
      (node (ref "C14") (pin "1") (pinfunction "1_1") (pintype "passive"))
      (node (ref "C15") (pin "1") (pinfunction "1_1") (pintype "passive"))
      (node (ref "C16") (pin "1") (pinfunction "1_1") (pintype "passive"))
      (node (ref "C22") (pin "1") (pinfunction "1_1") (pintype "passive"))
      (node (ref "C23") (pin "1") (pinfunction "1_1") (pintype "passive"))
      (node (ref "C24") (pin "1") (pinfunction "1_1") (pintype "passive"))
      (node (ref "C25") (pin "1") (pinfunction "1_1") (pintype "passive"))
      (node (ref "C26") (pin "2") (pinfunction "2_2") (pintype "passive"))
      (node (ref "C5") (pin "1") (pinfunction "1_1") (pintype "passive"))
      (node (ref "C8") (pin "1") (pinfunction "1_1") (pintype "passive"))
      (node (ref "D1") (pin "A") (pinfunction "A_A") (pintype "passive"))
      (node (ref "EMIFILTER1") (pin "1") (pinfunction "IN/OUT_1") (pintype "bidirectional"))
      (node (ref "EMIFILTER2") (pin "1") (pinfunction "IN/OUT_1") (pintype "bidirectional"))
      (node (ref "IC1") (pin "B3") (pinfunction "VCCIO0_B3") (pintype "bidirectional"))
      (node (ref "IC1") (pin "B4") (pinfunction "VPP2V5_B4") (pintype "bidirectional"))
      (node (ref "IC1") (pin "E3") (pinfunction "VCCIO2_E3") (pintype "bidirectional"))
      (node (ref "IC1") (pin "E4") (pinfunction "SPI_VCCIO1_E4") (pintype "bidirectional"))
      (node (ref "IC2") (pin "1") (pinfunction "VOUT_1") (pintype "bidirectional"))
      (node (ref "IC3") (pin "20") (pinfunction "VCCIO_1_20") (pintype "bidirectional"))
      (node (ref "IC3") (pin "31") (pinfunction "VCCIO_2_31") (pintype "bidirectional"))
      (node (ref "IC3") (pin "42") (pinfunction "VCCIO_3_42") (pintype "bidirectional"))
      (node (ref "IC3") (pin "50") (pinfunction "VREGIN_50") (pintype "bidirectional"))
      (node (ref "IC3") (pin "56") (pinfunction "VCCIO_4_56") (pintype "bidirectional"))
      (node (ref "IC4") (pin "6") (pinfunction "VCC_6") (pintype "power_in"))
      (node (ref "IC5") (pin "7") (pinfunction "~{HOLD}_7") (pintype "bidirectional"))
      (node (ref "IC5") (pin "8") (pinfunction "VCC_8") (pintype "power_in"))
      (node (ref "J1") (pin "1") (pinfunction "1_1") (pintype "passive"))
      (node (ref "PROGRAMMER") (pin "VCC") (pinfunction "VCC_VCC") (pintype "power_in"))
      (node (ref "R1") (pin "2") (pinfunction "2_2") (pintype "passive"))
      (node (ref "R11") (pin "2") (pinfunction "2_2") (pintype "passive"))
      (node (ref "R12") (pin "2") (pinfunction "2_2") (pintype "passive"))
      (node (ref "R13") (pin "2") (pinfunction "2_2") (pintype "passive"))
      (node (ref "R15") (pin "2") (pinfunction "2_2") (pintype "passive"))
      (node (ref "R17") (pin "2") (pinfunction "2_2") (pintype "passive"))
      (node (ref "R18") (pin "1") (pinfunction "1_1") (pintype "passive"))
      (node (ref "R23") (pin "1") (pinfunction "1_1") (pintype "passive"))
      (node (ref "R24") (pin "1") (pinfunction "1_1") (pintype "passive"))
      (node (ref "R4") (pin "2") (pinfunction "2_2") (pintype "passive"))
      (node (ref "R5") (pin "1") (pinfunction "1_1") (pintype "passive"))
      (node (ref "R7") (pin "2") (pinfunction "2_2") (pintype "passive"))
      (node (ref "R8") (pin "1") (pinfunction "1_1") (pintype "passive"))
      (node (ref "R9") (pin "2") (pinfunction "2_2") (pintype "passive"))
      (node (ref "U$1") (pin "VCC") (pinfunction "VCC_VCC") (pintype "power_in"))
      (node (ref "U2") (pin "2") (pinfunction "3V3_2") (pintype "bidirectional"))
    )
    (net (code "89") (name "VCC-FPGA-PLL") (class "Default")
      (node (ref "C27") (pin "1") (pinfunction "1_1") (pintype "passive"))
      (node (ref "C28") (pin "1") (pinfunction "1_1") (pintype "passive"))
      (node (ref "IC1") (pin "D3") (pinfunction "VCC_D3") (pintype "bidirectional"))
      (node (ref "IC1") (pin "D4") (pinfunction "VCCPLL_D4") (pintype "bidirectional"))
      (node (ref "R20") (pin "2") (pinfunction "2_2") (pintype "passive"))
    )
    (net (code "90") (name "VCC1.8") (class "Default")
      (node (ref "C10") (pin "1") (pinfunction "1_1") (pintype "passive"))
      (node (ref "C12") (pin "1") (pinfunction "1_1") (pintype "passive"))
      (node (ref "C17") (pin "1") (pinfunction "1_1") (pintype "passive"))
      (node (ref "C9") (pin "1") (pinfunction "1_1") (pintype "passive"))
      (node (ref "IC3") (pin "12") (pinfunction "VCORE_1_12") (pintype "bidirectional"))
      (node (ref "IC3") (pin "37") (pinfunction "VCORE_2_37") (pintype "bidirectional"))
      (node (ref "IC3") (pin "49") (pinfunction "VREGOUT_49") (pintype "bidirectional"))
      (node (ref "IC3") (pin "64") (pinfunction "VCORE_3_64") (pintype "bidirectional"))
    )
    (net (code "91") (name "VCC5") (class "Default")
      (node (ref "C2") (pin "1") (pinfunction "1_1") (pintype "passive"))
      (node (ref "R2") (pin "2") (pinfunction "2_2") (pintype "passive"))
      (node (ref "U$2") (pin "+5V") (pinfunction "+5V_+5V") (pintype "bidirectional"))
      (node (ref "U$4") (pin "4") (pinfunction "VDD_4") (pintype "bidirectional"))
    )
    (net (code "92") (name "unconnected-(IC1-IOT_25A-PadA3)") (class "Default")
      (node (ref "IC1") (pin "A3") (pinfunction "IOT_25A_A3") (pintype "bidirectional"))
    )
    (net (code "93") (name "unconnected-(IC2-ADJ-Pad8)") (class "Default")
      (node (ref "IC2") (pin "8") (pinfunction "ADJ_8") (pintype "bidirectional"))
    )
    (net (code "94") (name "unconnected-(IC3-ACBUS0-Pad26)") (class "Default")
      (node (ref "IC3") (pin "26") (pinfunction "ACBUS0_26") (pintype "bidirectional"))
    )
    (net (code "95") (name "unconnected-(IC3-ACBUS1-Pad27)") (class "Default")
      (node (ref "IC3") (pin "27") (pinfunction "ACBUS1_27") (pintype "bidirectional"))
    )
    (net (code "96") (name "unconnected-(IC3-ACBUS2-Pad28)") (class "Default")
      (node (ref "IC3") (pin "28") (pinfunction "ACBUS2_28") (pintype "bidirectional"))
    )
    (net (code "97") (name "unconnected-(IC3-ACBUS3-Pad29)") (class "Default")
      (node (ref "IC3") (pin "29") (pinfunction "ACBUS3_29") (pintype "bidirectional"))
    )
    (net (code "98") (name "unconnected-(IC3-ACBUS4-Pad30)") (class "Default")
      (node (ref "IC3") (pin "30") (pinfunction "ACBUS4_30") (pintype "bidirectional"))
    )
    (net (code "99") (name "unconnected-(IC3-ACBUS5-Pad32)") (class "Default")
      (node (ref "IC3") (pin "32") (pinfunction "ACBUS5_32") (pintype "bidirectional"))
    )
    (net (code "100") (name "unconnected-(IC3-ACBUS6-Pad33)") (class "Default")
      (node (ref "IC3") (pin "33") (pinfunction "ACBUS6_33") (pintype "bidirectional"))
    )
    (net (code "101") (name "unconnected-(IC3-ACBUS7-Pad34)") (class "Default")
      (node (ref "IC3") (pin "34") (pinfunction "ACBUS7_34") (pintype "bidirectional"))
    )
    (net (code "102") (name "unconnected-(IC3-ADBUS4-Pad21)") (class "Default")
      (node (ref "IC3") (pin "21") (pinfunction "ADBUS4_21") (pintype "bidirectional"))
    )
    (net (code "103") (name "unconnected-(IC3-ADBUS5-Pad22)") (class "Default")
      (node (ref "IC3") (pin "22") (pinfunction "ADBUS5_22") (pintype "bidirectional"))
    )
    (net (code "104") (name "unconnected-(IC3-ADBUS6-Pad23)") (class "Default")
      (node (ref "IC3") (pin "23") (pinfunction "ADBUS6_23") (pintype "bidirectional"))
    )
    (net (code "105") (name "unconnected-(IC3-ADBUS7-Pad24)") (class "Default")
      (node (ref "IC3") (pin "24") (pinfunction "ADBUS7_24") (pintype "bidirectional"))
    )
    (net (code "106") (name "unconnected-(IC3-BCBUS0-Pad48)") (class "Default")
      (node (ref "IC3") (pin "48") (pinfunction "BCBUS0_48") (pintype "bidirectional"))
    )
    (net (code "107") (name "unconnected-(IC3-BCBUS1-Pad52)") (class "Default")
      (node (ref "IC3") (pin "52") (pinfunction "BCBUS1_52") (pintype "bidirectional"))
    )
    (net (code "108") (name "unconnected-(IC3-BCBUS2-Pad53)") (class "Default")
      (node (ref "IC3") (pin "53") (pinfunction "BCBUS2_53") (pintype "bidirectional"))
    )
    (net (code "109") (name "unconnected-(IC3-BCBUS5-Pad57)") (class "Default")
      (node (ref "IC3") (pin "57") (pinfunction "BCBUS5_57") (pintype "bidirectional"))
    )
    (net (code "110") (name "unconnected-(IC3-BCBUS6-Pad58)") (class "Default")
      (node (ref "IC3") (pin "58") (pinfunction "BCBUS6_58") (pintype "bidirectional"))
    )
    (net (code "111") (name "unconnected-(IC3-BDBUS4-Pad43)") (class "Default")
      (node (ref "IC3") (pin "43") (pinfunction "BDBUS4_43") (pintype "bidirectional"))
    )
    (net (code "112") (name "unconnected-(IC3-BDBUS5-Pad44)") (class "Default")
      (node (ref "IC3") (pin "44") (pinfunction "BDBUS5_44") (pintype "bidirectional"))
    )
    (net (code "113") (name "unconnected-(IC3-BDBUS6-Pad45)") (class "Default")
      (node (ref "IC3") (pin "45") (pinfunction "BDBUS6_45") (pintype "bidirectional"))
    )
    (net (code "114") (name "unconnected-(IC3-BDBUS7-Pad46)") (class "Default")
      (node (ref "IC3") (pin "46") (pinfunction "BDBUS7_46") (pintype "bidirectional"))
    )
    (net (code "115") (name "unconnected-(J5-Pad1)") (class "Default")
      (node (ref "J5") (pin "1") (pinfunction "1_1") (pintype "passive"))
    )
    (net (code "116") (name "unconnected-(J5-Pad3)") (class "Default")
      (node (ref "J5") (pin "3") (pinfunction "3_3") (pintype "passive"))
    )
    (net (code "117") (name "unconnected-(J5-Pad5)") (class "Default")
      (node (ref "J5") (pin "5") (pinfunction "5_5") (pintype "passive"))
    )
    (net (code "118") (name "unconnected-(J5-Pad7)") (class "Default")
      (node (ref "J5") (pin "7") (pinfunction "7_7") (pintype "passive"))
    )
    (net (code "119") (name "unconnected-(U$1-NC_1-PadNC1)") (class "Default")
      (node (ref "U$1") (pin "NC1") (pinfunction "NC_1_NC1") (pintype "no_connect"))
    )
    (net (code "120") (name "unconnected-(U$1-NC_2-PadNC2)") (class "Default")
      (node (ref "U$1") (pin "NC2") (pinfunction "NC_2_NC2") (pintype "no_connect"))
    )
    (net (code "121") (name "unconnected-(U$1-NC_3-PadNC3)") (class "Default")
      (node (ref "U$1") (pin "NC3") (pinfunction "NC_3_NC3") (pintype "no_connect"))
    )
    (net (code "122") (name "unconnected-(U$1-NC_4-PadNC4)") (class "Default")
      (node (ref "U$1") (pin "NC4") (pinfunction "NC_4_NC4") (pintype "no_connect"))
    )
    (net (code "123") (name "unconnected-(U$2-PadID)") (class "Default")
      (node (ref "U$2") (pin "ID") (pinfunction "ID_ID") (pintype "bidirectional"))
    )
    (net (code "124") (name "unconnected-(U$3-PadP3)") (class "Default")
      (node (ref "U$3") (pin "P3") (pinfunction "P3_P3") (pintype "bidirectional"))
    )
    (net (code "125") (name "unconnected-(U$3-PadP4)") (class "Default")
      (node (ref "U$3") (pin "P4") (pinfunction "P4_P4") (pintype "bidirectional"))
    )
    (net (code "126") (name "unconnected-(U$3-PadP5)") (class "Default")
      (node (ref "U$3") (pin "P5") (pinfunction "P5_P5") (pintype "bidirectional"))
    )
    (net (code "127") (name "unconnected-(U2-CLK-Pad20)") (class "Default")
      (node (ref "U2") (pin "20") (pinfunction "CLK_20") (pintype "bidirectional"))
    )
    (net (code "128") (name "unconnected-(U2-CMD-Pad19)") (class "Default")
      (node (ref "U2") (pin "19") (pinfunction "CMD_19") (pintype "bidirectional"))
    )
    (net (code "129") (name "unconnected-(U2-NC-Pad32)") (class "Default")
      (node (ref "U2") (pin "32") (pinfunction "NC_32") (pintype "bidirectional"))
    )
    (net (code "130") (name "unconnected-(U2-PadGND)") (class "Default")
      (node (ref "U2") (pin "GND") (pinfunction "GND_GND") (pintype "bidirectional"))
    )
    (net (code "131") (name "unconnected-(U2-SD1-Pad22)") (class "Default")
      (node (ref "U2") (pin "22") (pinfunction "SD1_22") (pintype "bidirectional"))
    )
    (net (code "132") (name "unconnected-(U2-SD2-Pad17)") (class "Default")
      (node (ref "U2") (pin "17") (pinfunction "SD2_17") (pintype "bidirectional"))
    )
    (net (code "133") (name "unconnected-(U2-SD3-Pad18)") (class "Default")
      (node (ref "U2") (pin "18") (pinfunction "SD3_18") (pintype "bidirectional"))
    )
    (net (code "134") (name "unconnected-(U2-SDO-Pad21)") (class "Default")
      (node (ref "U2") (pin "21") (pinfunction "SDO_21") (pintype "bidirectional"))
    )
  )
)
